# OneBellInterfaceRevA.net
KiCad netlist of a schematic drawn in EAGLE
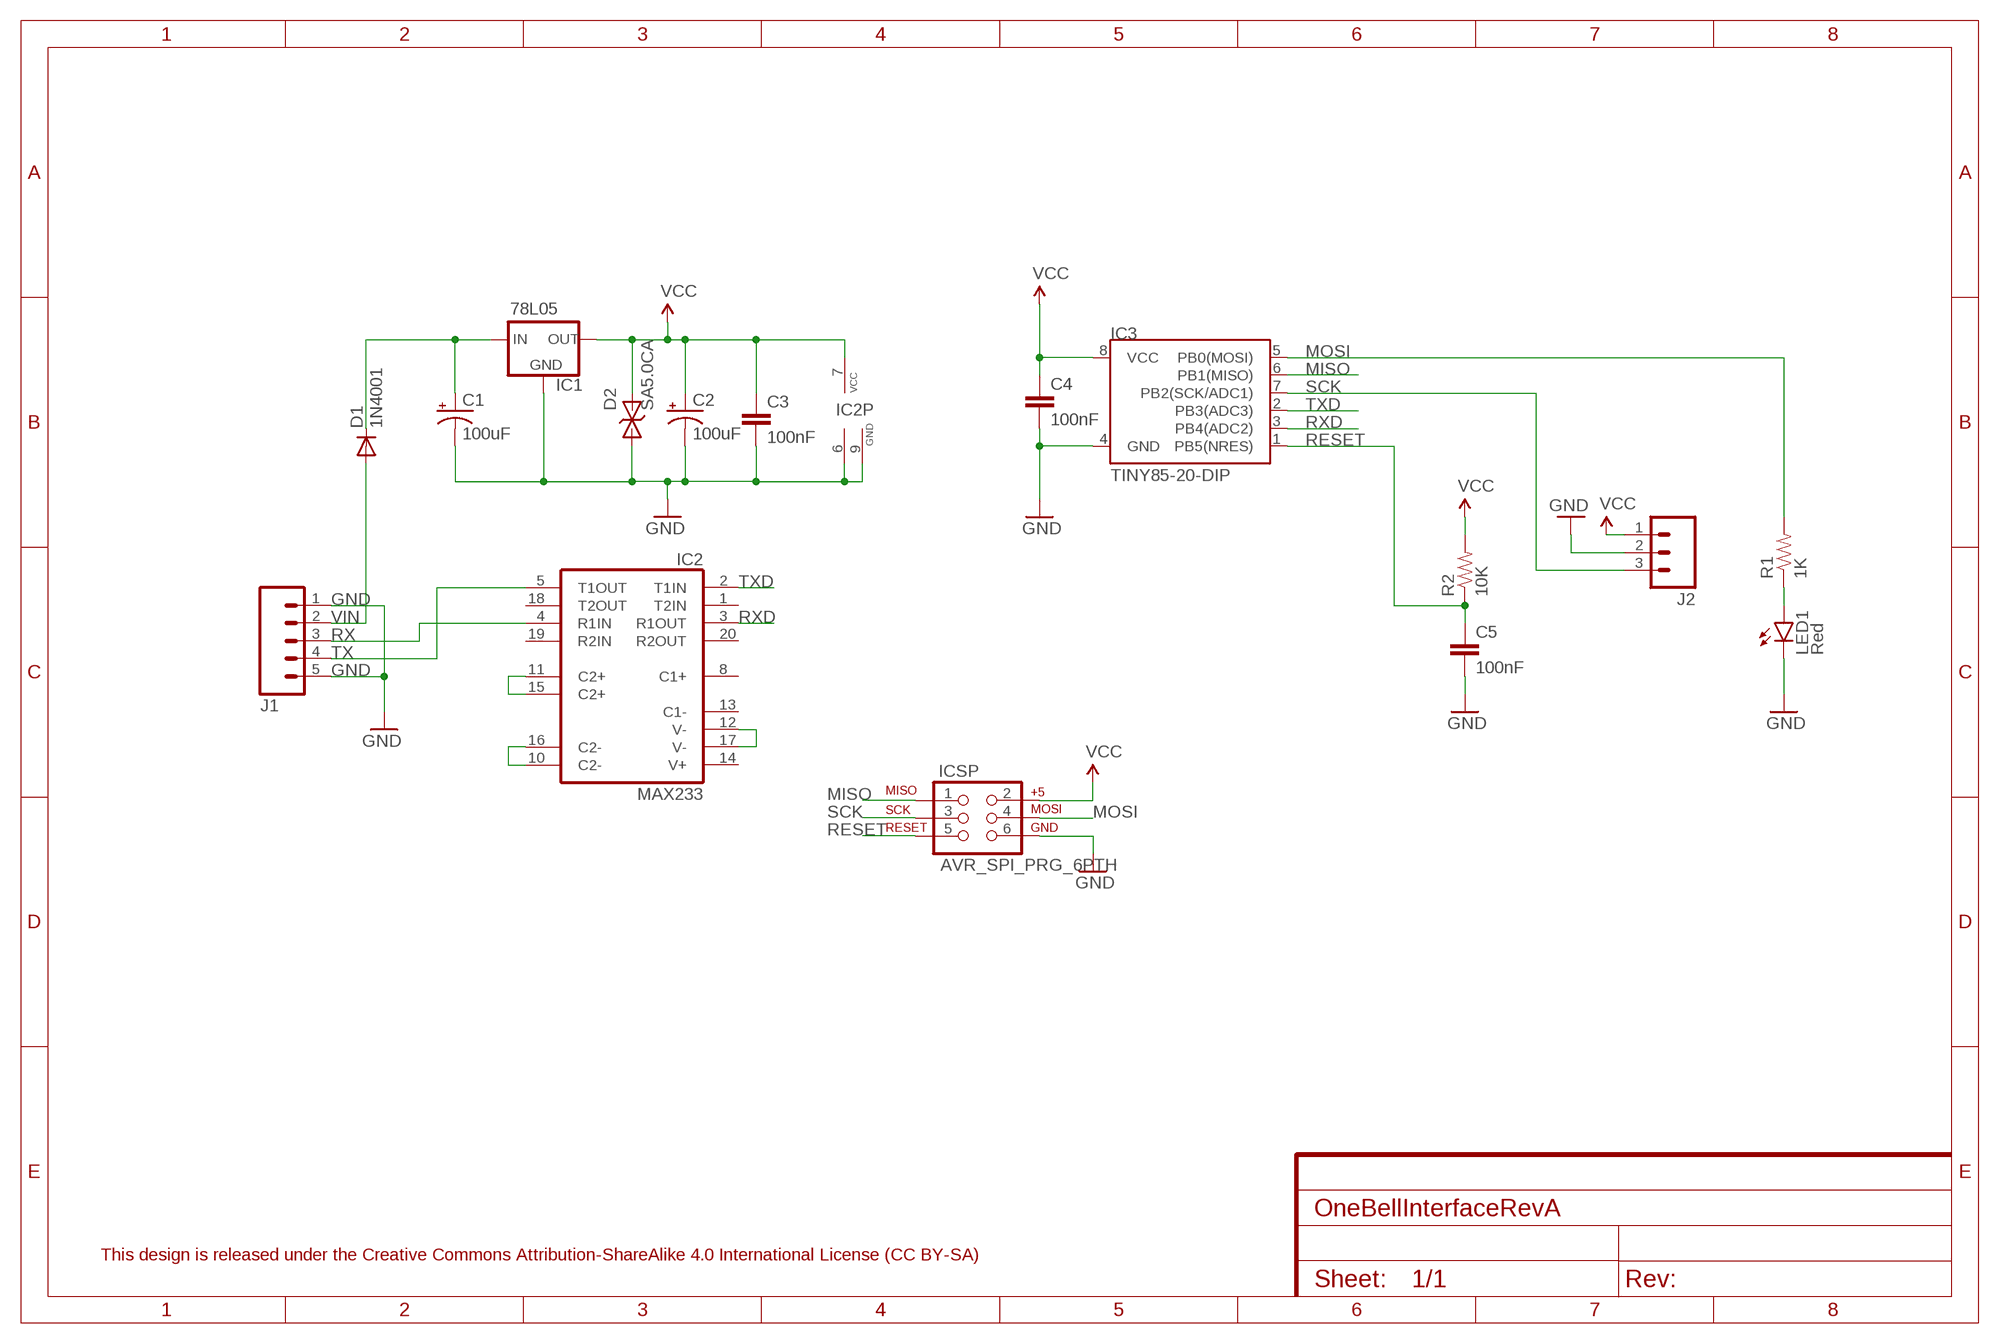
[diagram p0: schematic, sheet 1]

(export (version "E")
  (design (tool "Eeschema 10.0.6"))
  (components
    (comp (ref "C1")
      (value "100uF")
      (footprint "eagle-import:CPOL-RADIAL-100UF-25V")
      (libsource (lib "eagle-import") (part "CAP_POLPTH1"))
    )
    (comp (ref "C2")
      (value "100uF")
      (footprint "eagle-import:CPOL-RADIAL-100UF-25V")
      (libsource (lib "eagle-import") (part "CAP_POLPTH1"))
    )
    (comp (ref "C3")
      (value "100nF")
      (footprint "eagle-import:CAP-PTH-SMALL")
      (libsource (lib "eagle-import") (part "CAPPTH"))
    )
    (comp (ref "C4")
      (value "100nF")
      (footprint "eagle-import:CAP-PTH-SMALL")
      (libsource (lib "eagle-import") (part "CAPPTH"))
    )
    (comp (ref "C5")
      (value "100nF")
      (footprint "eagle-import:CAP-PTH-SMALL")
      (libsource (lib "eagle-import") (part "CAPPTH"))
    )
    (comp (ref "D1")
      (value "1N4001")
      (footprint "eagle-import:DO41_DIODE")
      (libsource (lib "eagle-import") (part "1N4001"))
    )
    (comp (ref "D2")
      (value "SA5.0CA")
      (footprint "eagle-import:DO41_TVS")
      (libsource (lib "eagle-import") (part "SA5.0CA"))
    )
    (comp (ref "IC1")
      (value "78L05")
      (footprint "eagle-import:TO-92")
      (libsource (lib "eagle-import") (part "V_REG_78XXTO-92_UNTESTED"))
    )
    (comp (ref "IC2")
      (value "MAX233")
      (footprint "eagle-import:DIL20")
      (fields (field (name "MPN") "MAX233ACPP+G36"))
      (libsource (lib "eagle-import") (part "MAX233"))
    )
    (comp (ref "IC3")
      (value "TINY85-20-DIP")
      (footprint "eagle-import:DIL08")
      (libsource (lib "eagle-import") (part "ATTINY45DIL08_LONG_PADS"))
    )
    (comp (ref "ICSP")
      (value "AVR_SPI_PRG_6PTH")
      (footprint "eagle-import:2X3")
      (libsource (lib "eagle-import") (part "AVR_SPI_PRG_6PTH"))
    )
    (comp (ref "J1")
      (value "M05PTH")
      (footprint "eagle-import:1X05")
      (libsource (lib "eagle-import") (part "M05PTH"))
    )
    (comp (ref "J2")
      (value "M03PTH")
      (footprint "eagle-import:1X03")
      (libsource (lib "eagle-import") (part "M03PTH"))
    )
    (comp (ref "LED1")
      (value "Red")
      (footprint "eagle-import:LED3MM")
      (libsource (lib "eagle-import") (part "LED3MM"))
    )
    (comp (ref "R1")
      (value "1K")
      (footprint "eagle-import:AXIAL-0.4")
      (libsource (lib "eagle-import") (part "RESISTORPTH-1/4W"))
    )
    (comp (ref "R2")
      (value "10K")
      (footprint "eagle-import:AXIAL-0.4")
      (libsource (lib "eagle-import") (part "RESISTORPTH-1/4W"))
    )
  )
  (nets
    (net (code "1") (name "/MISO") (class "Default")
      (node (ref "IC3") (pin "6") (pinfunction "PB1(MISO)_6") (pintype "bidirectional"))
      (node (ref "ICSP") (pin "1") (pinfunction "1_1") (pintype "passive"))
    )
    (net (code "2") (name "/MOSI") (class "Default")
      (node (ref "IC3") (pin "5") (pinfunction "PB0(MOSI)_5") (pintype "bidirectional"))
      (node (ref "ICSP") (pin "4") (pinfunction "4_4") (pintype "passive"))
      (node (ref "R1") (pin "P$2") (pinfunction "2_P$2") (pintype "passive"))
    )
    (net (code "3") (name "/RESET") (class "Default")
      (node (ref "C5") (pin "1") (pinfunction "1_1") (pintype "passive"))
      (node (ref "IC3") (pin "1") (pinfunction "PB5(NRES)_1") (pintype "bidirectional"))
      (node (ref "ICSP") (pin "5") (pinfunction "5_5") (pintype "passive"))
      (node (ref "R2") (pin "P$1") (pinfunction "1_P$1") (pintype "passive"))
    )
    (net (code "4") (name "/RX") (class "Default")
      (node (ref "IC2") (pin "4") (pinfunction "R1IN_4") (pintype "input"))
      (node (ref "J1") (pin "3") (pinfunction "3_3") (pintype "passive"))
    )
    (net (code "5") (name "/RXD") (class "Default")
      (node (ref "IC2") (pin "3") (pinfunction "R1OUT_3") (pintype "output"))
      (node (ref "IC3") (pin "3") (pinfunction "PB4(ADC2)_3") (pintype "bidirectional"))
    )
    (net (code "6") (name "/SCK") (class "Default")
      (node (ref "IC3") (pin "7") (pinfunction "PB2(SCK/ADC1)_7") (pintype "bidirectional"))
      (node (ref "ICSP") (pin "3") (pinfunction "3_3") (pintype "passive"))
      (node (ref "J2") (pin "3") (pinfunction "3_3") (pintype "passive"))
    )
    (net (code "7") (name "/TX") (class "Default")
      (node (ref "IC2") (pin "5") (pinfunction "T1OUT_5") (pintype "output"))
      (node (ref "J1") (pin "4") (pinfunction "4_4") (pintype "passive"))
    )
    (net (code "8") (name "/TXD") (class "Default")
      (node (ref "IC2") (pin "2") (pinfunction "T1IN_2") (pintype "input"))
      (node (ref "IC3") (pin "2") (pinfunction "PB3(ADC3)_2") (pintype "bidirectional"))
    )
    (net (code "9") (name "/VIN") (class "Default")
      (node (ref "D1") (pin "A") (pinfunction "A_A") (pintype "passive"))
      (node (ref "J1") (pin "2") (pinfunction "2_2") (pintype "passive"))
    )
    (net (code "10") (name "GND") (class "Default")
      (node (ref "C1") (pin "2") (pinfunction "-_2") (pintype "passive"))
      (node (ref "C2") (pin "2") (pinfunction "-_2") (pintype "passive"))
      (node (ref "C3") (pin "2") (pinfunction "2_2") (pintype "passive"))
      (node (ref "C4") (pin "2") (pinfunction "2_2") (pintype "passive"))
      (node (ref "C5") (pin "2") (pinfunction "2_2") (pintype "passive"))
      (node (ref "D2") (pin "A") (pinfunction "A_A") (pintype "passive"))
      (node (ref "IC1") (pin "2") (pinfunction "GND_2") (pintype "input"))
      (node (ref "IC2") (pin "6") (pinfunction "GND_6") (pintype "power_in"))
      (node (ref "IC2") (pin "9") (pinfunction "GND_9") (pintype "power_in"))
      (node (ref "IC3") (pin "4") (pinfunction "GND_4") (pintype "bidirectional"))
      (node (ref "ICSP") (pin "6") (pinfunction "6_6") (pintype "passive"))
      (node (ref "J1") (pin "1") (pinfunction "1_1") (pintype "passive"))
      (node (ref "J1") (pin "5") (pinfunction "5_5") (pintype "passive"))
      (node (ref "J2") (pin "2") (pinfunction "2_2") (pintype "passive"))
      (node (ref "LED1") (pin "K") (pinfunction "C_K") (pintype "passive"))
    )
    (net (code "11") (name "Net-(C1-+)") (class "Default")
      (node (ref "C1") (pin "1") (pinfunction "+_1") (pintype "passive"))
      (node (ref "D1") (pin "C") (pinfunction "C_C") (pintype "passive"))
      (node (ref "IC1") (pin "3") (pinfunction "IN_3") (pintype "input"))
    )
    (net (code "12") (name "Net-(IC2A-C2+-Pad11)") (class "Default")
      (node (ref "IC2") (pin "11") (pinfunction "C2+_11") (pintype "bidirectional"))
      (node (ref "IC2") (pin "15") (pinfunction "C2+_15") (pintype "bidirectional"))
    )
    (net (code "13") (name "Net-(IC2A-C2--Pad10)") (class "Default")
      (node (ref "IC2") (pin "10") (pinfunction "C2-_10") (pintype "bidirectional"))
      (node (ref "IC2") (pin "16") (pinfunction "C2-_16") (pintype "bidirectional"))
    )
    (net (code "14") (name "Net-(IC2A-V--Pad12)") (class "Default")
      (node (ref "IC2") (pin "12") (pinfunction "V-_12") (pintype "bidirectional"))
      (node (ref "IC2") (pin "17") (pinfunction "V-_17") (pintype "bidirectional"))
    )
    (net (code "15") (name "Net-(R1-1)") (class "Default")
      (node (ref "LED1") (pin "A") (pinfunction "A_A") (pintype "passive"))
      (node (ref "R1") (pin "P$1") (pinfunction "1_P$1") (pintype "passive"))
    )
    (net (code "16") (name "VCC") (class "Default")
      (node (ref "C2") (pin "1") (pinfunction "+_1") (pintype "passive"))
      (node (ref "C3") (pin "1") (pinfunction "1_1") (pintype "passive"))
      (node (ref "C4") (pin "1") (pinfunction "1_1") (pintype "passive"))
      (node (ref "D2") (pin "C") (pinfunction "C_C") (pintype "passive"))
      (node (ref "IC1") (pin "1") (pinfunction "OUT_1") (pintype "passive"))
      (node (ref "IC2") (pin "7") (pinfunction "VCC_7") (pintype "power_in"))
      (node (ref "IC3") (pin "8") (pinfunction "VCC_8") (pintype "bidirectional"))
      (node (ref "ICSP") (pin "2") (pinfunction "2_2") (pintype "passive"))
      (node (ref "J2") (pin "1") (pinfunction "1_1") (pintype "passive"))
      (node (ref "R2") (pin "P$2") (pinfunction "2_P$2") (pintype "passive"))
    )
    (net (code "17") (name "unconnected-(IC2A-C1+-Pad8)") (class "Default")
      (node (ref "IC2") (pin "8") (pinfunction "C1+_8") (pintype "bidirectional"))
    )
    (net (code "18") (name "unconnected-(IC2A-C1--Pad13)") (class "Default")
      (node (ref "IC2") (pin "13") (pinfunction "C1-_13") (pintype "bidirectional"))
    )
    (net (code "19") (name "unconnected-(IC2A-R2IN-Pad19)") (class "Default")
      (node (ref "IC2") (pin "19") (pinfunction "R2IN_19") (pintype "input"))
    )
    (net (code "20") (name "unconnected-(IC2A-R2OUT-Pad20)") (class "Default")
      (node (ref "IC2") (pin "20") (pinfunction "R2OUT_20") (pintype "output"))
    )
    (net (code "21") (name "unconnected-(IC2A-T2IN-Pad1)") (class "Default")
      (node (ref "IC2") (pin "1") (pinfunction "T2IN_1") (pintype "input"))
    )
    (net (code "22") (name "unconnected-(IC2A-T2OUT-Pad18)") (class "Default")
      (node (ref "IC2") (pin "18") (pinfunction "T2OUT_18") (pintype "output"))
    )
    (net (code "23") (name "unconnected-(IC2A-V+-Pad14)") (class "Default")
      (node (ref "IC2") (pin "14") (pinfunction "V+_14") (pintype "bidirectional"))
    )
  )
)
